# ProPrj___2025-12-22.net
KiCad netlist of a schematic drawn in EasyEDA Pro
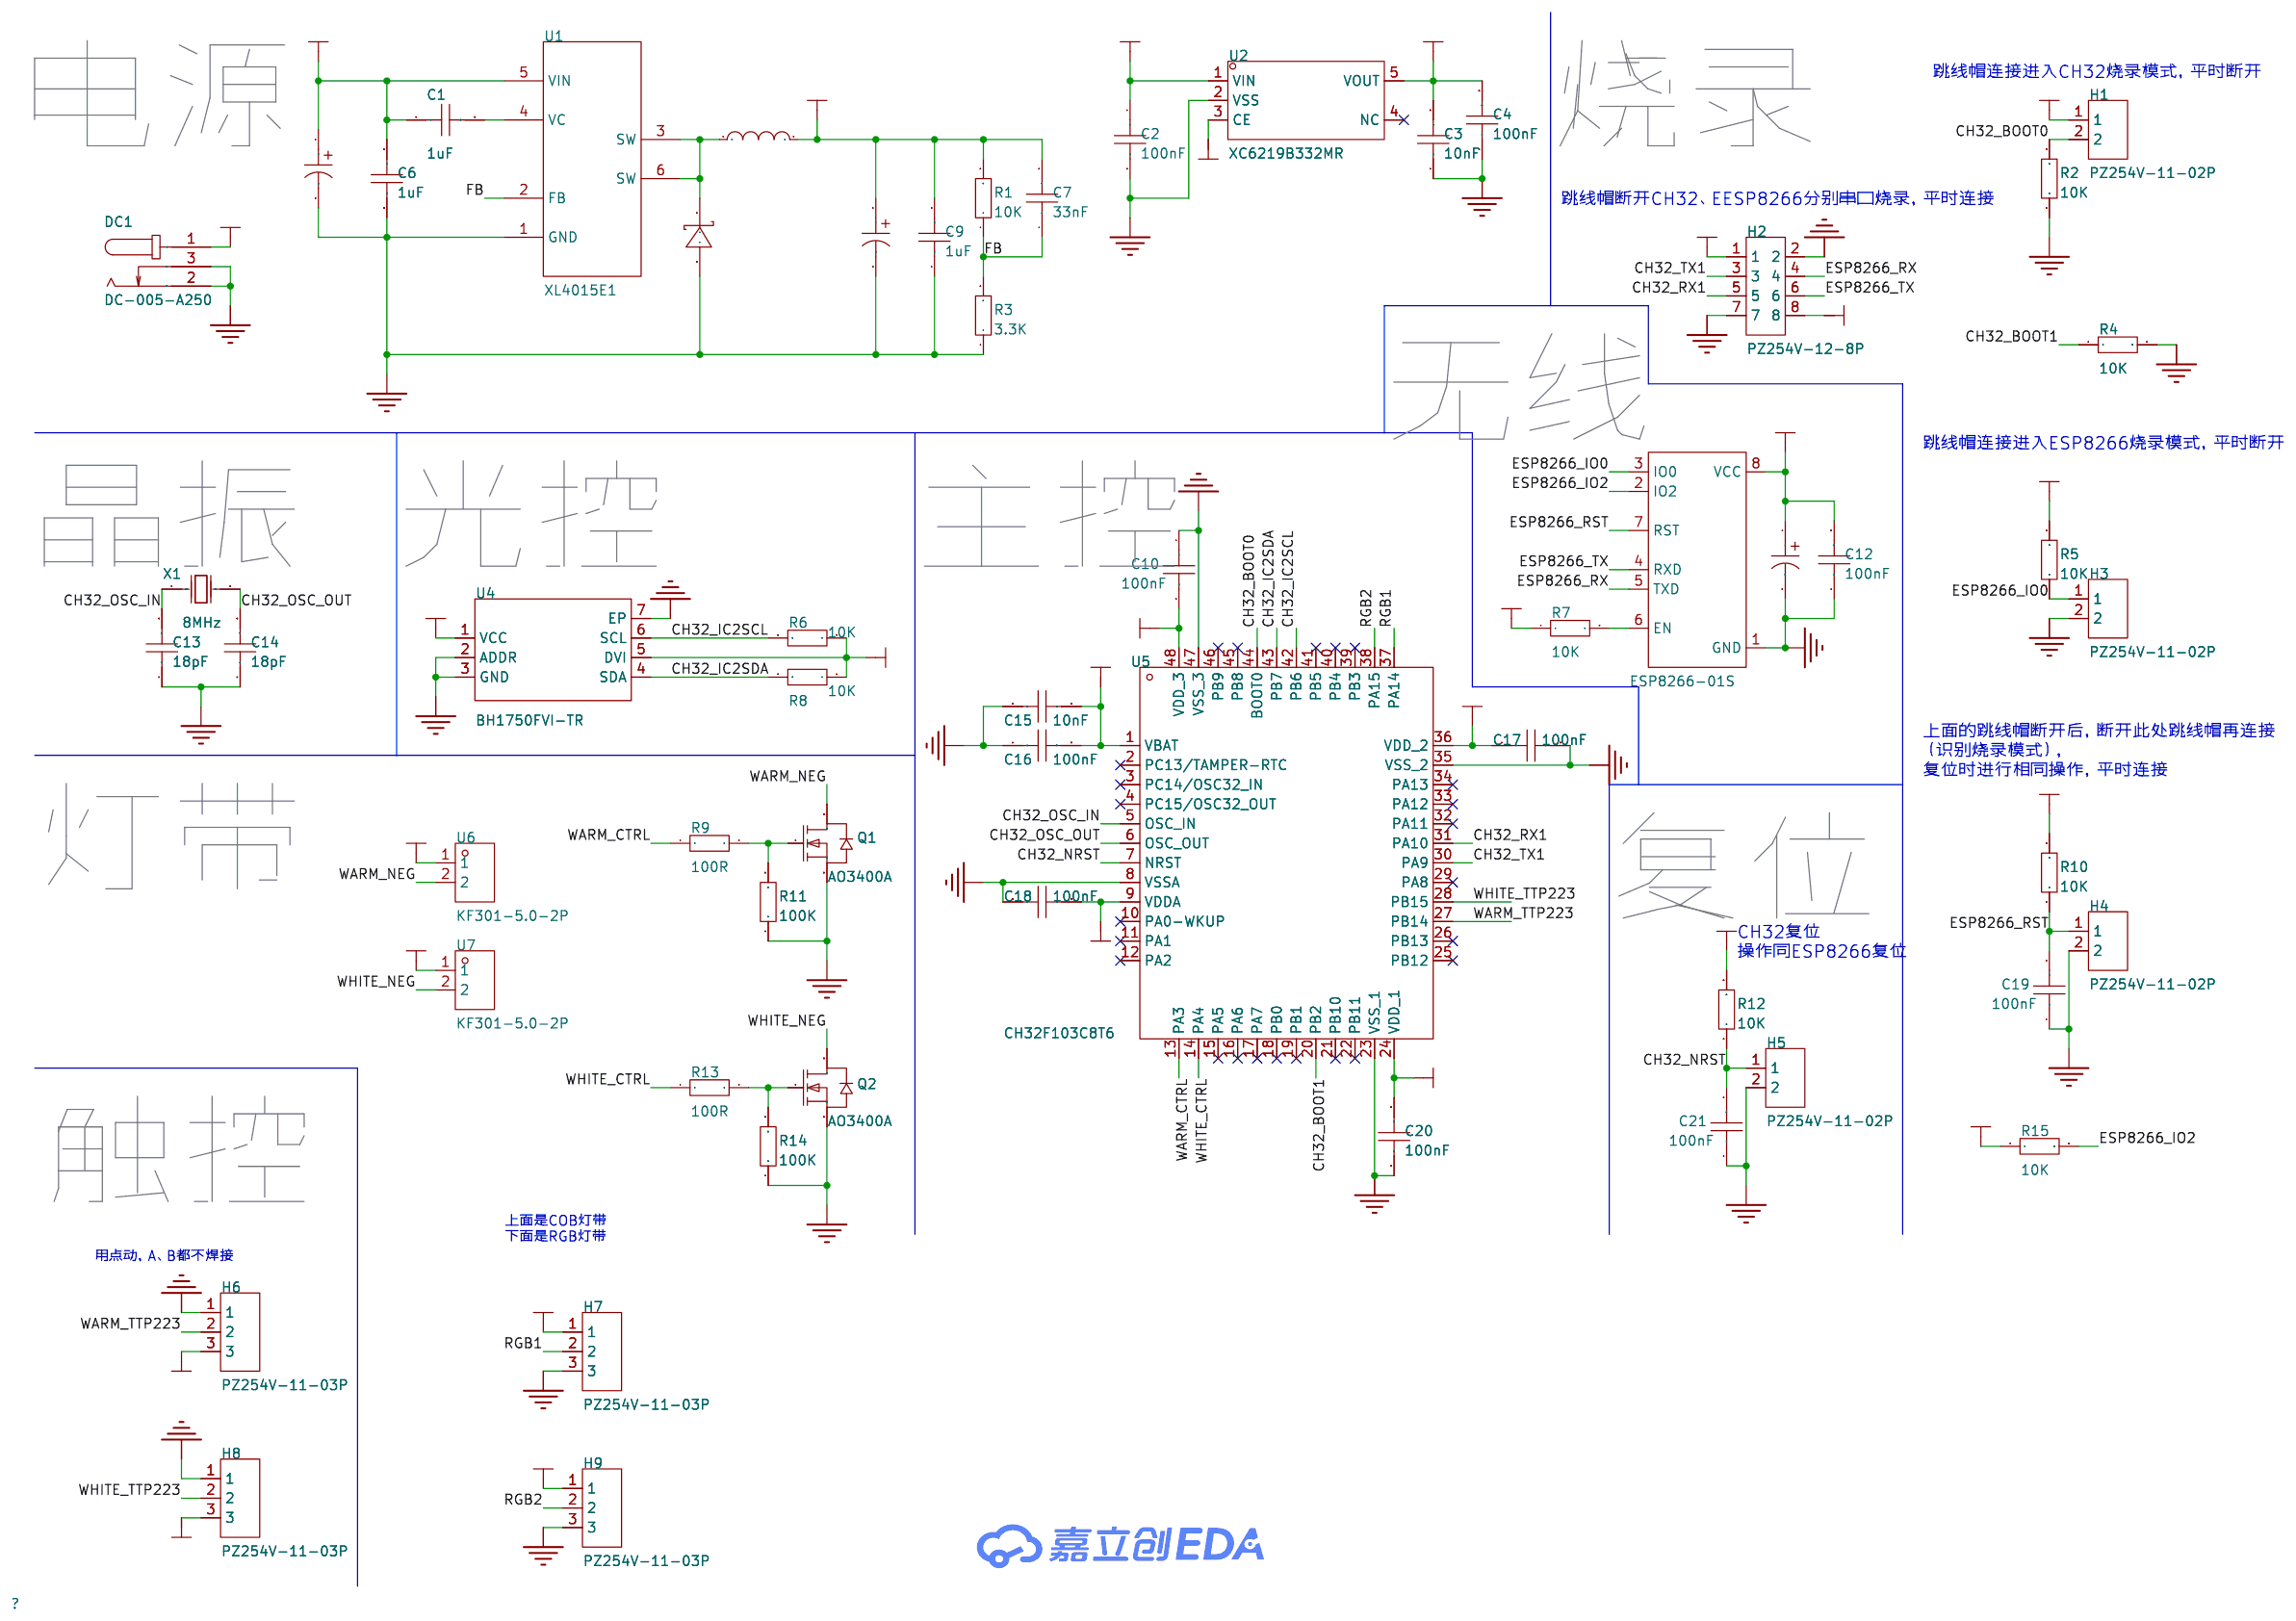
[diagram p0: schematic sheet]

(export (version "E")
  (design (tool "Eeschema 10.0.6"))
  (components
    (comp (ref "C1")
      (value "1uF")
      (footprint "easyedapro:C0805")
      (libsource (lib "easyedapro") (part "Capacitance"))
    )
    (comp (ref "C2")
      (value "100nF")
      (footprint "easyedapro:C0805")
      (libsource (lib "easyedapro") (part "Capacitance"))
    )
    (comp (ref "C3")
      (value "10nF")
      (footprint "easyedapro:C0805")
      (libsource (lib "easyedapro") (part "Capacitance"))
    )
    (comp (ref "C4")
      (value "100nF")
      (footprint "easyedapro:C0805")
      (libsource (lib "easyedapro") (part "Capacitance"))
    )
    (comp (ref "C5")
      (value "220uF")
      (footprint "easyedapro:贴片铝电解电容220uF_35V_8*10.5mm")
      (description "淘宝深圳市优信电子科技有限公司购买")
      (libsource (lib "easyedapro") (part "贴片铝电解电容220uF_35V_8*10.5mm"))
    )
    (comp (ref "C6")
      (value "1uF")
      (footprint "easyedapro:C0805")
      (libsource (lib "easyedapro") (part "Capacitance"))
    )
    (comp (ref "C7")
      (value "33nF")
      (footprint "easyedapro:C0805")
      (libsource (lib "easyedapro") (part "Capacitance"))
    )
    (comp (ref "C8")
      (value "470uF")
      (footprint "easyedapro:贴片铝电解电容470uF_10V_6.3*7.7mm")
      (description "淘宝深圳市优信电子科技有限公司购买")
      (libsource (lib "easyedapro") (part "贴片铝电解电容470uF_10V_6.3*7.7mm"))
    )
    (comp (ref "C9")
      (value "1uF")
      (footprint "easyedapro:C0805")
      (libsource (lib "easyedapro") (part "Capacitance"))
    )
    (comp (ref "C10")
      (value "100nF")
      (footprint "easyedapro:C0805")
      (libsource (lib "easyedapro") (part "Capacitance"))
    )
    (comp (ref "C11")
      (value "100uF")
      (footprint "easyedapro:贴片铝电解电容100uF_10V_5*5.4mm")
      (description "淘宝深圳市优信电子科技有限公司购买")
      (libsource (lib "easyedapro") (part "贴片铝电解电容100uF_10V_5*5.4mm"))
    )
    (comp (ref "C12")
      (value "100nF")
      (footprint "easyedapro:C0805")
      (libsource (lib "easyedapro") (part "Capacitance"))
    )
    (comp (ref "C13")
      (value "18pF")
      (footprint "easyedapro:C0805")
      (libsource (lib "easyedapro") (part "Capacitance"))
    )
    (comp (ref "C14")
      (value "18pF")
      (footprint "easyedapro:C0805")
      (libsource (lib "easyedapro") (part "Capacitance"))
    )
    (comp (ref "C15")
      (value "10nF")
      (footprint "easyedapro:C0805")
      (libsource (lib "easyedapro") (part "Capacitance"))
    )
    (comp (ref "C16")
      (value "100nF")
      (footprint "easyedapro:C0805")
      (libsource (lib "easyedapro") (part "Capacitance"))
    )
    (comp (ref "C17")
      (value "100nF")
      (footprint "easyedapro:C0805")
      (libsource (lib "easyedapro") (part "Capacitance"))
    )
    (comp (ref "C18")
      (value "100nF")
      (footprint "easyedapro:C0805")
      (libsource (lib "easyedapro") (part "Capacitance"))
    )
    (comp (ref "C19")
      (value "100nF")
      (footprint "easyedapro:C0805")
      (libsource (lib "easyedapro") (part "Capacitance"))
    )
    (comp (ref "C20")
      (value "100nF")
      (footprint "easyedapro:C0805")
      (libsource (lib "easyedapro") (part "Capacitance"))
    )
    (comp (ref "C21")
      (value "100nF")
      (footprint "easyedapro:C0805")
      (libsource (lib "easyedapro") (part "Capacitance"))
    )
    (comp (ref "D1")
      (value "SS54")
      (footprint "easyedapro:SS54SMB40V5AD0-214")
      (description "淘宝优信电子购买")
      (libsource (lib "easyedapro") (part "SS54SMB40V5AD0-214"))
    )
    (comp (ref "DC1")
      (value "DC-005-A250")
      (footprint "easyedapro:DC-IN-TH_DC-005-A250")
      (description "连接器类型:DC电源插座;安装方式:弯插;触点内径:2.5mm;触点外径:6.3mm;额定电流:3A;额定电压:30V;工作温度范围:-20°C~+70°C;")
      (fields (field (name "Manufacturer") "XUNPU(讯普)"))
      (libsource (lib "easyedapro") (part "DC-005-A250"))
    )
    (comp (ref "H1")
      (value "PZ254V-11-02P")
      (footprint "easyedapro:HDR-TH_2P-P2.54-V-M")
      (fields (field (name "Manufacturer") "XFCN(兴飞)"))
      (libsource (lib "easyedapro") (part "PZ254V-11-02P"))
    )
    (comp (ref "H2")
      (value "PZ254V-12-8P")
      (footprint "easyedapro:HDR-TH_8P-P2.54-V-M-R2-C4-S2.54")
      (fields (field (name "Manufacturer") "XFCN(兴飞)"))
      (libsource (lib "easyedapro") (part "PZ254V-12-8P"))
    )
    (comp (ref "H3")
      (value "PZ254V-11-02P")
      (footprint "easyedapro:HDR-TH_2P-P2.54-V-M")
      (fields (field (name "Manufacturer") "XFCN(兴飞)"))
      (libsource (lib "easyedapro") (part "PZ254V-11-02P"))
    )
    (comp (ref "H4")
      (value "PZ254V-11-02P")
      (footprint "easyedapro:HDR-TH_2P-P2.54-V-M")
      (fields (field (name "Manufacturer") "XFCN(兴飞)"))
      (libsource (lib "easyedapro") (part "PZ254V-11-02P"))
    )
    (comp (ref "H5")
      (value "PZ254V-11-02P")
      (footprint "easyedapro:HDR-TH_2P-P2.54-V-M")
      (fields (field (name "Manufacturer") "XFCN(兴飞)"))
      (libsource (lib "easyedapro") (part "PZ254V-11-02P"))
    )
    (comp (ref "H6")
      (value "PZ254V-11-03P")
      (footprint "easyedapro:HDR-TH_3P-P2.54-V-M")
      (fields (field (name "Manufacturer") "XFCN(兴飞)"))
      (libsource (lib "easyedapro") (part "PZ254V-11-03P_C2937625"))
    )
    (comp (ref "H7")
      (value "PZ254V-11-03P")
      (footprint "easyedapro:HDR-TH_3P-P2.54-V-M")
      (fields (field (name "Manufacturer") "XFCN(兴飞)"))
      (libsource (lib "easyedapro") (part "PZ254V-11-03P_C2937625"))
    )
    (comp (ref "H8")
      (value "PZ254V-11-03P")
      (footprint "easyedapro:HDR-TH_3P-P2.54-V-M")
      (fields (field (name "Manufacturer") "XFCN(兴飞)"))
      (libsource (lib "easyedapro") (part "PZ254V-11-03P_C2937625"))
    )
    (comp (ref "H9")
      (value "PZ254V-11-03P")
      (footprint "easyedapro:HDR-TH_3P-P2.54-V-M")
      (fields (field (name "Manufacturer") "XFCN(兴飞)"))
      (libsource (lib "easyedapro") (part "PZ254V-11-03P_C2937625"))
    )
    (comp (ref "L1")
      (value "68uH")
      (footprint "easyedapro:65125铁硅铝电感/68uH(1.0线)")
      (description "淘宝优信电子购买")
      (libsource (lib "easyedapro") (part "65125铁硅铝电感/68uH(1.0线)"))
    )
    (comp (ref "Q1")
      (value "AO3400A")
      (footprint "easyedapro:SOT-23-3_L2.9-W1.3-P1.90-LS2.4-BR")
      (fields (field (name "Manufacturer") "UMW(友台半导体)"))
      (libsource (lib "easyedapro") (part "AO3400A_C347475"))
    )
    (comp (ref "Q2")
      (value "AO3400A")
      (footprint "easyedapro:SOT-23-3_L2.9-W1.3-P1.90-LS2.4-BR")
      (fields (field (name "Manufacturer") "UMW(友台半导体)"))
      (libsource (lib "easyedapro") (part "AO3400A_C347475"))
    )
    (comp (ref "R1") (value "10K") (footprint "easyedapro:R0603") (libsource (lib "easyedapro") (part "电阻")))
    (comp (ref "R2") (value "10K") (footprint "easyedapro:R0603") (libsource (lib "easyedapro") (part "电阻")))
    (comp (ref "R3") (value "3.3K") (footprint "easyedapro:R0603") (libsource (lib "easyedapro") (part "电阻")))
    (comp (ref "R4") (value "10K") (footprint "easyedapro:R0603") (libsource (lib "easyedapro") (part "电阻")))
    (comp (ref "R5") (value "10K") (footprint "easyedapro:R0603") (libsource (lib "easyedapro") (part "电阻")))
    (comp (ref "R6") (value "10K") (footprint "easyedapro:R0603") (libsource (lib "easyedapro") (part "电阻")))
    (comp (ref "R7") (value "10K") (footprint "easyedapro:R0603") (libsource (lib "easyedapro") (part "电阻")))
    (comp (ref "R8") (value "10K") (footprint "easyedapro:R0603") (libsource (lib "easyedapro") (part "电阻")))
    (comp (ref "R9") (value "100R") (footprint "easyedapro:R0603") (libsource (lib "easyedapro") (part "电阻")))
    (comp (ref "R10") (value "10K") (footprint "easyedapro:R0603") (libsource (lib "easyedapro") (part "电阻")))
    (comp (ref "R11")
      (value "100K")
      (footprint "easyedapro:R0603")
      (libsource (lib "easyedapro") (part "电阻"))
    )
    (comp (ref "R12") (value "10K") (footprint "easyedapro:R0603") (libsource (lib "easyedapro") (part "电阻")))
    (comp (ref "R13")
      (value "100R")
      (footprint "easyedapro:R0603")
      (libsource (lib "easyedapro") (part "电阻"))
    )
    (comp (ref "R14")
      (value "100K")
      (footprint "easyedapro:R0603")
      (libsource (lib "easyedapro") (part "电阻"))
    )
    (comp (ref "R15") (value "10K") (footprint "easyedapro:R0603") (libsource (lib "easyedapro") (part "电阻")))
    (comp (ref "U1")
      (value "XL4015E1")
      (footprint "easyedapro:TO-263-5_L10.2-W8.9-P1.70-TL")
      (description "功能类型:降压型;工作电压:8V~36V;输出电压:1.25V~32V;输出电流:5A;输出类型:可调;")
      (fields (field (name "Manufacturer") "XLSEMI(芯龙)"))
      (libsource (lib "easyedapro") (part "XL4015E1"))
    )
    (comp (ref "U2")
      (value "XC6219B332MR")
      (footprint "easyedapro:SOT-23-5_L3.0-W1.7-P0.95-LS2.8-BR")
      (description "输出类型:固定;工作电压:7V;输出电压:3.3V;输出电流:300mA;电源纹波抑制比(PSRR):40dB@(1kHz);输出极性:正极;")
      (fields (field (name "Manufacturer") "UMW(友台半导体)"))
      (libsource (lib "easyedapro") (part "XC6219B332MR_C347386"))
    )
    (comp (ref "U3")
      (value "ESP8266-01S")
      (footprint "easyedapro:ESP8266ESP-01S")
      (description "淘宝深圳市优信电子科技有限公司购买")
      (libsource (lib "easyedapro") (part "ESP8266ESP-01S"))
    )
    (comp (ref "U4")
      (value "BH1750FVI-TR")
      (footprint "easyedapro:WSOF-6_L2.6-W1.6-P0.50-TL-EP")
      (description "检测颜色:-;接口类型:I2C;")
      (fields (field (name "Manufacturer") "ROHM(罗姆)"))
      (libsource (lib "easyedapro") (part "BH1750FVI-TR"))
    )
    (comp (ref "U5")
      (value "CH32F103C8T6")
      (footprint "easyedapro:LQFP-48_L7.0-W7.0-P0.50-LS9.0-BL")
      (description "CPU内核:ARM-M3;程序存储容量:64KB;RAM总容量:20KB;GPIO端口数量:37;工作电压范围:2.7V~5.5V;CPU最大主频:72MHz;程序存储器类型:-;应用领域:-;")
      (fields (field (name "Manufacturer") "WCH(南京沁恒)"))
      (libsource (lib "easyedapro") (part "CH32F103C8T6"))
    )
    (comp (ref "U6")
      (value "KF301-5.0-2P")
      (footprint "easyedapro:CONN-TH_P5.00_KF301-5.0-2P")
      (fields (field (name "Manufacturer") "KEFA(科发)"))
      (libsource (lib "easyedapro") (part "KF301-5.0-2P"))
    )
    (comp (ref "U7")
      (value "KF301-5.0-2P")
      (footprint "easyedapro:CONN-TH_P5.00_KF301-5.0-2P")
      (fields (field (name "Manufacturer") "KEFA(科发)"))
      (libsource (lib "easyedapro") (part "KF301-5.0-2P"))
    )
    (comp (ref "X1")
      (value "8MHz")
      (footprint "easyedapro:CRYSTAL-SMD_L5.0-W3.2")
      (description "晶振类型:贴片晶振;频率:8MHz;常温频差:±10ppm;负载电容:20pF;频率稳定度:±20ppm;")
      (fields (field (name "Manufacturer Part") "X50328MSB2GI") (field (name "Manufacturer") "YXC(扬兴晶振)"))
      (libsource (lib "easyedapro") (part "X50328MSB2GI"))
    )
  )
  (nets
    (net (code "1") (name "/CH32_BOOT0") (class "Default")
      (node (ref "H1") (pin "2") (pinfunction "2_2") (pintype "unspecified"))
      (node (ref "R2") (pin "2") (pinfunction "2_2") (pintype "input"))
      (node (ref "U5") (pin "44") (pinfunction "BOOT0_44") (pintype "unspecified"))
    )
    (net (code "2") (name "/CH32_BOOT1") (class "Default")
      (node (ref "R4") (pin "1") (pinfunction "1_1") (pintype "input"))
      (node (ref "U5") (pin "20") (pinfunction "PB2_20") (pintype "unspecified"))
    )
    (net (code "3") (name "/CH32_IC2SCL") (class "Default")
      (node (ref "R6") (pin "2") (pinfunction "2_2") (pintype "input"))
      (node (ref "U4") (pin "6") (pinfunction "SCL_6") (pintype "unspecified"))
      (node (ref "U5") (pin "42") (pinfunction "PB6_42") (pintype "unspecified"))
    )
    (net (code "4") (name "/CH32_IC2SDA") (class "Default")
      (node (ref "R8") (pin "2") (pinfunction "2_2") (pintype "input"))
      (node (ref "U4") (pin "4") (pinfunction "SDA_4") (pintype "unspecified"))
      (node (ref "U5") (pin "43") (pinfunction "PB7_43") (pintype "unspecified"))
    )
    (net (code "5") (name "/CH32_NRST") (class "Default")
      (node (ref "C21") (pin "2") (pinfunction "2_2") (pintype "input"))
      (node (ref "H5") (pin "1") (pinfunction "1_1") (pintype "unspecified"))
      (node (ref "R12") (pin "1") (pinfunction "1_1") (pintype "input"))
      (node (ref "U5") (pin "7") (pinfunction "NRST_7") (pintype "unspecified"))
    )
    (net (code "6") (name "/CH32_OSC_IN") (class "Default")
      (node (ref "C13") (pin "2") (pinfunction "2_2") (pintype "input"))
      (node (ref "U5") (pin "5") (pinfunction "OSC_IN_5") (pintype "unspecified"))
      (node (ref "X1") (pin "1") (pinfunction "OSC1_1") (pintype "input"))
    )
    (net (code "7") (name "/CH32_OSC_OUT") (class "Default")
      (node (ref "C14") (pin "2") (pinfunction "2_2") (pintype "input"))
      (node (ref "U5") (pin "6") (pinfunction "OSC_OUT_6") (pintype "unspecified"))
      (node (ref "X1") (pin "2") (pinfunction "OSC2_2") (pintype "input"))
    )
    (net (code "8") (name "/CH32_RX1") (class "Default")
      (node (ref "H2") (pin "5") (pinfunction "5_5") (pintype "unspecified"))
      (node (ref "U5") (pin "31") (pinfunction "PA10_31") (pintype "unspecified"))
    )
    (net (code "9") (name "/CH32_TX1") (class "Default")
      (node (ref "H2") (pin "3") (pinfunction "3_3") (pintype "unspecified"))
      (node (ref "U5") (pin "30") (pinfunction "PA9_30") (pintype "unspecified"))
    )
    (net (code "10") (name "/ESP8266_IO0") (class "Default")
      (node (ref "H3") (pin "1") (pinfunction "1_1") (pintype "unspecified"))
      (node (ref "R5") (pin "1") (pinfunction "1_1") (pintype "input"))
      (node (ref "U3") (pin "3") (pinfunction "IO0_3") (pintype "unspecified"))
    )
    (net (code "11") (name "/ESP8266_IO2") (class "Default")
      (node (ref "R15") (pin "2") (pinfunction "2_2") (pintype "input"))
      (node (ref "U3") (pin "2") (pinfunction "IO2_2") (pintype "unspecified"))
    )
    (net (code "12") (name "/ESP8266_RST") (class "Default")
      (node (ref "C19") (pin "2") (pinfunction "2_2") (pintype "input"))
      (node (ref "H4") (pin "1") (pinfunction "1_1") (pintype "unspecified"))
      (node (ref "R10") (pin "1") (pinfunction "1_1") (pintype "input"))
      (node (ref "U3") (pin "7") (pinfunction "RST_7") (pintype "unspecified"))
    )
    (net (code "13") (name "/ESP8266_RX") (class "Default")
      (node (ref "H2") (pin "4") (pinfunction "4_4") (pintype "unspecified"))
      (node (ref "U3") (pin "5") (pinfunction "TXD_5") (pintype "unspecified"))
    )
    (net (code "14") (name "/ESP8266_TX") (class "Default")
      (node (ref "H2") (pin "6") (pinfunction "6_6") (pintype "unspecified"))
      (node (ref "U3") (pin "4") (pinfunction "RXD_4") (pintype "unspecified"))
    )
    (net (code "15") (name "/FB") (class "Default")
      (node (ref "C7") (pin "1") (pinfunction "1_1") (pintype "input"))
      (node (ref "R1") (pin "1") (pinfunction "1_1") (pintype "input"))
      (node (ref "R3") (pin "2") (pinfunction "2_2") (pintype "input"))
      (node (ref "U1") (pin "2") (pinfunction "FB_2") (pintype "unspecified"))
    )
    (net (code "16") (name "/RGB1") (class "Default")
      (node (ref "H7") (pin "2") (pinfunction "2_2") (pintype "unspecified"))
      (node (ref "U5") (pin "37") (pinfunction "PA14_37") (pintype "unspecified"))
    )
    (net (code "17") (name "/RGB2") (class "Default")
      (node (ref "H9") (pin "2") (pinfunction "2_2") (pintype "unspecified"))
      (node (ref "U5") (pin "38") (pinfunction "PA15_38") (pintype "unspecified"))
    )
    (net (code "18") (name "/WARM_CTRL") (class "Default")
      (node (ref "R9") (pin "1") (pinfunction "1_1") (pintype "input"))
      (node (ref "U5") (pin "13") (pinfunction "PA3_13") (pintype "unspecified"))
    )
    (net (code "19") (name "/WARM_NEG") (class "Default")
      (node (ref "Q1") (pin "3") (pinfunction "D_3") (pintype "unspecified"))
      (node (ref "U6") (pin "2") (pinfunction "2_2") (pintype "unspecified"))
    )
    (net (code "20") (name "/WARM_TTP223") (class "Default")
      (node (ref "H6") (pin "2") (pinfunction "2_2") (pintype "unspecified"))
      (node (ref "U5") (pin "27") (pinfunction "PB14_27") (pintype "unspecified"))
    )
    (net (code "21") (name "/WHITE_CTRL") (class "Default")
      (node (ref "R13") (pin "1") (pinfunction "1_1") (pintype "input"))
      (node (ref "U5") (pin "14") (pinfunction "PA4_14") (pintype "unspecified"))
    )
    (net (code "22") (name "/WHITE_NEG") (class "Default")
      (node (ref "Q2") (pin "3") (pinfunction "D_3") (pintype "unspecified"))
      (node (ref "U7") (pin "2") (pinfunction "2_2") (pintype "unspecified"))
    )
    (net (code "23") (name "/WHITE_TTP223") (class "Default")
      (node (ref "H8") (pin "2") (pinfunction "2_2") (pintype "unspecified"))
      (node (ref "U5") (pin "28") (pinfunction "PB15_28") (pintype "unspecified"))
    )
    (net (code "24") (name "3.3V") (class "Default")
      (node (ref "C10") (pin "2") (pinfunction "2_2") (pintype "input"))
      (node (ref "C11") (pin "1") (pinfunction "1_1") (pintype "input"))
      (node (ref "C12") (pin "2") (pinfunction "2_2") (pintype "input"))
      (node (ref "C15") (pin "2") (pinfunction "2_2") (pintype "input"))
      (node (ref "C16") (pin "2") (pinfunction "2_2") (pintype "input"))
      (node (ref "C17") (pin "1") (pinfunction "1_1") (pintype "input"))
      (node (ref "C18") (pin "2") (pinfunction "2_2") (pintype "input"))
      (node (ref "C20") (pin "2") (pinfunction "2_2") (pintype "input"))
      (node (ref "C3") (pin "2") (pinfunction "2_2") (pintype "input"))
      (node (ref "C4") (pin "2") (pinfunction "2_2") (pintype "input"))
      (node (ref "H1") (pin "1") (pinfunction "1_1") (pintype "unspecified"))
      (node (ref "H2") (pin "1") (pinfunction "1_1") (pintype "unspecified"))
      (node (ref "H2") (pin "8") (pinfunction "8_8") (pintype "unspecified"))
      (node (ref "H6") (pin "3") (pinfunction "3_3") (pintype "unspecified"))
      (node (ref "H8") (pin "3") (pinfunction "3_3") (pintype "unspecified"))
      (node (ref "R10") (pin "2") (pinfunction "2_2") (pintype "input"))
      (node (ref "R12") (pin "2") (pinfunction "2_2") (pintype "input"))
      (node (ref "R15") (pin "1") (pinfunction "1_1") (pintype "input"))
      (node (ref "R5") (pin "2") (pinfunction "2_2") (pintype "input"))
      (node (ref "R6") (pin "1") (pinfunction "1_1") (pintype "input"))
      (node (ref "R7") (pin "1") (pinfunction "1_1") (pintype "input"))
      (node (ref "R8") (pin "1") (pinfunction "1_1") (pintype "input"))
      (node (ref "U2") (pin "5") (pinfunction "VOUT_5") (pintype "unspecified"))
      (node (ref "U3") (pin "8") (pinfunction "VCC_8") (pintype "unspecified"))
      (node (ref "U4") (pin "1") (pinfunction "VCC_1") (pintype "unspecified"))
      (node (ref "U4") (pin "5") (pinfunction "DVI_5") (pintype "unspecified"))
      (node (ref "U5") (pin "1") (pinfunction "VBAT_1") (pintype "unspecified"))
      (node (ref "U5") (pin "24") (pinfunction "VDD_1_24") (pintype "unspecified"))
      (node (ref "U5") (pin "36") (pinfunction "VDD_2_36") (pintype "unspecified"))
      (node (ref "U5") (pin "48") (pinfunction "VDD_3_48") (pintype "unspecified"))
      (node (ref "U5") (pin "9") (pinfunction "VDDA_9") (pintype "unspecified"))
    )
    (net (code "25") (name "5V") (class "Default")
      (node (ref "C2") (pin "1") (pinfunction "1_1") (pintype "input"))
      (node (ref "C7") (pin "2") (pinfunction "2_2") (pintype "input"))
      (node (ref "C8") (pin "1") (pinfunction "1_1") (pintype "input"))
      (node (ref "C9") (pin "2") (pinfunction "2_2") (pintype "input"))
      (node (ref "H7") (pin "1") (pinfunction "1_1") (pintype "unspecified"))
      (node (ref "H9") (pin "1") (pinfunction "1_1") (pintype "unspecified"))
      (node (ref "L1") (pin "2") (pinfunction "2_2") (pintype "unspecified"))
      (node (ref "R1") (pin "2") (pinfunction "2_2") (pintype "input"))
      (node (ref "U2") (pin "1") (pinfunction "VIN_1") (pintype "unspecified"))
      (node (ref "U2") (pin "3") (pinfunction "CE_3") (pintype "unspecified"))
    )
    (net (code "26") (name "24V") (class "Default")
      (node (ref "C1") (pin "1") (pinfunction "1_1") (pintype "input"))
      (node (ref "C5") (pin "1") (pinfunction "1_1") (pintype "input"))
      (node (ref "C6") (pin "1") (pinfunction "1_1") (pintype "input"))
      (node (ref "DC1") (pin "1") (pinfunction "1_1") (pintype "input"))
      (node (ref "U1") (pin "5") (pinfunction "VIN_5") (pintype "unspecified"))
      (node (ref "U6") (pin "1") (pinfunction "1_1") (pintype "unspecified"))
      (node (ref "U7") (pin "1") (pinfunction "1_1") (pintype "unspecified"))
    )
    (net (code "27") (name "GND") (class "Default")
      (node (ref "C10") (pin "1") (pinfunction "1_1") (pintype "input"))
      (node (ref "C11") (pin "2") (pinfunction "2_2") (pintype "input"))
      (node (ref "C12") (pin "1") (pinfunction "1_1") (pintype "input"))
      (node (ref "C13") (pin "1") (pinfunction "1_1") (pintype "input"))
      (node (ref "C14") (pin "1") (pinfunction "1_1") (pintype "input"))
      (node (ref "C15") (pin "1") (pinfunction "1_1") (pintype "input"))
      (node (ref "C16") (pin "1") (pinfunction "1_1") (pintype "input"))
      (node (ref "C17") (pin "2") (pinfunction "2_2") (pintype "input"))
      (node (ref "C18") (pin "1") (pinfunction "1_1") (pintype "input"))
      (node (ref "C19") (pin "1") (pinfunction "1_1") (pintype "input"))
      (node (ref "C2") (pin "2") (pinfunction "2_2") (pintype "input"))
      (node (ref "C20") (pin "1") (pinfunction "1_1") (pintype "input"))
      (node (ref "C21") (pin "1") (pinfunction "1_1") (pintype "input"))
      (node (ref "C3") (pin "1") (pinfunction "1_1") (pintype "input"))
      (node (ref "C4") (pin "1") (pinfunction "1_1") (pintype "input"))
      (node (ref "C5") (pin "2") (pinfunction "2_2") (pintype "input"))
      (node (ref "C6") (pin "2") (pinfunction "2_2") (pintype "input"))
      (node (ref "C8") (pin "2") (pinfunction "2_2") (pintype "input"))
      (node (ref "C9") (pin "1") (pinfunction "1_1") (pintype "input"))
      (node (ref "D1") (pin "2") (pinfunction "A_2") (pintype "unspecified"))
      (node (ref "DC1") (pin "2") (pinfunction "2_2") (pintype "input"))
      (node (ref "DC1") (pin "3") (pinfunction "3_3") (pintype "input"))
      (node (ref "H2") (pin "2") (pinfunction "2_2") (pintype "unspecified"))
      (node (ref "H2") (pin "7") (pinfunction "7_7") (pintype "unspecified"))
      (node (ref "H3") (pin "2") (pinfunction "2_2") (pintype "unspecified"))
      (node (ref "H4") (pin "2") (pinfunction "2_2") (pintype "unspecified"))
      (node (ref "H5") (pin "2") (pinfunction "2_2") (pintype "unspecified"))
      (node (ref "H6") (pin "1") (pinfunction "1_1") (pintype "unspecified"))
      (node (ref "H7") (pin "3") (pinfunction "3_3") (pintype "unspecified"))
      (node (ref "H8") (pin "1") (pinfunction "1_1") (pintype "unspecified"))
      (node (ref "H9") (pin "3") (pinfunction "3_3") (pintype "unspecified"))
      (node (ref "Q1") (pin "2") (pinfunction "S_2") (pintype "unspecified"))
      (node (ref "Q2") (pin "2") (pinfunction "S_2") (pintype "unspecified"))
      (node (ref "R11") (pin "1") (pinfunction "1_1") (pintype "input"))
      (node (ref "R14") (pin "1") (pinfunction "1_1") (pintype "input"))
      (node (ref "R2") (pin "1") (pinfunction "1_1") (pintype "input"))
      (node (ref "R3") (pin "1") (pinfunction "1_1") (pintype "input"))
      (node (ref "R4") (pin "2") (pinfunction "2_2") (pintype "input"))
      (node (ref "U1") (pin "1") (pinfunction "GND_1") (pintype "unspecified"))
      (node (ref "U2") (pin "2") (pinfunction "VSS_2") (pintype "unspecified"))
      (node (ref "U3") (pin "1") (pinfunction "GND_1") (pintype "unspecified"))
      (node (ref "U4") (pin "2") (pinfunction "ADDR_2") (pintype "unspecified"))
      (node (ref "U4") (pin "3") (pinfunction "GND_3") (pintype "unspecified"))
      (node (ref "U4") (pin "7") (pinfunction "EP_7") (pintype "unspecified"))
      (node (ref "U5") (pin "23") (pinfunction "VSS_1_23") (pintype "unspecified"))
      (node (ref "U5") (pin "35") (pinfunction "VSS_2_35") (pintype "unspecified"))
      (node (ref "U5") (pin "47") (pinfunction "VSS_3_47") (pintype "unspecified"))
      (node (ref "U5") (pin "8") (pinfunction "VSSA_8") (pintype "unspecified"))
    )
    (net (code "28") (name "Net-(D1-K)") (class "Default")
      (node (ref "D1") (pin "1") (pinfunction "K_1") (pintype "unspecified"))
      (node (ref "L1") (pin "1") (pinfunction "1_1") (pintype "unspecified"))
      (node (ref "U1") (pin "3") (pinfunction "SW_3") (pintype "unspecified"))
      (node (ref "U1") (pin "6") (pinfunction "SW_6") (pintype "unspecified"))
    )
    (net (code "29") (name "Net-(Q1-G)") (class "Default")
      (node (ref "Q1") (pin "1") (pinfunction "G_1") (pintype "unspecified"))
      (node (ref "R11") (pin "2") (pinfunction "2_2") (pintype "input"))
      (node (ref "R9") (pin "2") (pinfunction "2_2") (pintype "input"))
    )
    (net (code "30") (name "Net-(Q2-G)") (class "Default")
      (node (ref "Q2") (pin "1") (pinfunction "G_1") (pintype "unspecified"))
      (node (ref "R13") (pin "2") (pinfunction "2_2") (pintype "input"))
      (node (ref "R14") (pin "2") (pinfunction "2_2") (pintype "input"))
    )
    (net (code "31") (name "Net-(U1-VC)") (class "Default")
      (node (ref "C1") (pin "2") (pinfunction "2_2") (pintype "input"))
      (node (ref "U1") (pin "4") (pinfunction "VC_4") (pintype "unspecified"))
    )
    (net (code "32") (name "Net-(U3-EN)") (class "Default")
      (node (ref "R7") (pin "2") (pinfunction "2_2") (pintype "input"))
      (node (ref "U3") (pin "6") (pinfunction "EN_6") (pintype "unspecified"))
    )
    (net (code "33") (name "unconnected-(U2-NC-Pad4)") (class "Default")
      (node (ref "U2") (pin "4") (pinfunction "NC_4") (pintype "unspecified+no_connect"))
    )
    (net (code "34") (name "unconnected-(U5-PA0-WKUP-Pad10)") (class "Default")
      (node (ref "U5") (pin "10") (pinfunction "PA0-WKUP_10") (pintype "unspecified+no_connect"))
    )
    (net (code "35") (name "unconnected-(U5-PA1-Pad11)") (class "Default")
      (node (ref "U5") (pin "11") (pinfunction "PA1_11") (pintype "unspecified+no_connect"))
    )
    (net (code "36") (name "unconnected-(U5-PA2-Pad12)") (class "Default")
      (node (ref "U5") (pin "12") (pinfunction "PA2_12") (pintype "unspecified+no_connect"))
    )
    (net (code "37") (name "unconnected-(U5-PA5-Pad15)") (class "Default")
      (node (ref "U5") (pin "15") (pinfunction "PA5_15") (pintype "unspecified+no_connect"))
    )
    (net (code "38") (name "unconnected-(U5-PA6-Pad16)") (class "Default")
      (node (ref "U5") (pin "16") (pinfunction "PA6_16") (pintype "unspecified+no_connect"))
    )
    (net (code "39") (name "unconnected-(U5-PA7-Pad17)") (class "Default")
      (node (ref "U5") (pin "17") (pinfunction "PA7_17") (pintype "unspecified+no_connect"))
    )
    (net (code "40") (name "unconnected-(U5-PA8-Pad29)") (class "Default")
      (node (ref "U5") (pin "29") (pinfunction "PA8_29") (pintype "unspecified+no_connect"))
    )
    (net (code "41") (name "unconnected-(U5-PA11-Pad32)") (class "Default")
      (node (ref "U5") (pin "32") (pinfunction "PA11_32") (pintype "unspecified+no_connect"))
    )
    (net (code "42") (name "unconnected-(U5-PA12-Pad33)") (class "Default")
      (node (ref "U5") (pin "33") (pinfunction "PA12_33") (pintype "unspecified+no_connect"))
    )
    (net (code "43") (name "unconnected-(U5-PA13-Pad34)") (class "Default")
      (node (ref "U5") (pin "34") (pinfunction "PA13_34") (pintype "unspecified+no_connect"))
    )
    (net (code "44") (name "unconnected-(U5-PB0-Pad18)") (class "Default")
      (node (ref "U5") (pin "18") (pinfunction "PB0_18") (pintype "unspecified+no_connect"))
    )
    (net (code "45") (name "unconnected-(U5-PB1-Pad19)") (class "Default")
      (node (ref "U5") (pin "19") (pinfunction "PB1_19") (pintype "unspecified+no_connect"))
    )
    (net (code "46") (name "unconnected-(U5-PB3-Pad39)") (class "Default")
      (node (ref "U5") (pin "39") (pinfunction "PB3_39") (pintype "unspecified+no_connect"))
    )
    (net (code "47") (name "unconnected-(U5-PB4-Pad40)") (class "Default")
      (node (ref "U5") (pin "40") (pinfunction "PB4_40") (pintype "unspecified+no_connect"))
    )
    (net (code "48") (name "unconnected-(U5-PB5-Pad41)") (class "Default")
      (node (ref "U5") (pin "41") (pinfunction "PB5_41") (pintype "unspecified+no_connect"))
    )
    (net (code "49") (name "unconnected-(U5-PB8-Pad45)") (class "Default")
      (node (ref "U5") (pin "45") (pinfunction "PB8_45") (pintype "unspecified+no_connect"))
    )
    (net (code "50") (name "unconnected-(U5-PB9-Pad46)") (class "Default")
      (node (ref "U5") (pin "46") (pinfunction "PB9_46") (pintype "unspecified+no_connect"))
    )
    (net (code "51") (name "unconnected-(U5-PB10-Pad21)") (class "Default")
      (node (ref "U5") (pin "21") (pinfunction "PB10_21") (pintype "unspecified+no_connect"))
    )
    (net (code "52") (name "unconnected-(U5-PB11-Pad22)") (class "Default")
      (node (ref "U5") (pin "22") (pinfunction "PB11_22") (pintype "unspecified+no_connect"))
    )
    (net (code "53") (name "unconnected-(U5-PB12-Pad25)") (class "Default")
      (node (ref "U5") (pin "25") (pinfunction "PB12_25") (pintype "unspecified+no_connect"))
    )
    (net (code "54") (name "unconnected-(U5-PB13-Pad26)") (class "Default")
      (node (ref "U5") (pin "26") (pinfunction "PB13_26") (pintype "unspecified+no_connect"))
    )
    (net (code "55") (name "unconnected-(U5-PC13{slash}TAMPER-RTC-Pad2)") (class "Default")
      (node (ref "U5") (pin "2") (pinfunction "PC13/TAMPER-RTC_2") (pintype "unspecified+no_connect"))
    )
    (net (code "56") (name "unconnected-(U5-PC14{slash}OSC32_IN-Pad3)") (class "Default")
      (node (ref "U5") (pin "3") (pinfunction "PC14/OSC32_IN_3") (pintype "unspecified+no_connect"))
    )
    (net (code "57") (name "unconnected-(U5-PC15{slash}OSC32_OUT-Pad4)") (class "Default")
      (node (ref "U5") (pin "4") (pinfunction "PC15/OSC32_OUT_4") (pintype "unspecified+no_connect"))
    )
  )
)
